# EX_POWER.net
KiCad netlist of a schematic drawn in Altium Designer
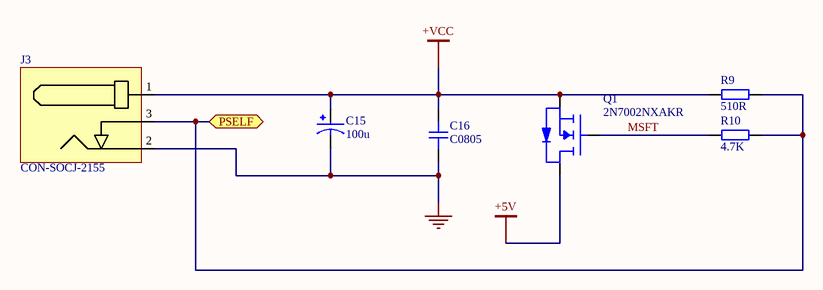
[diagram p0: EX_POWER.SchDoc]

(export (version "E")
  (design (tool "Eeschema 10.0.6"))
  (components
    (comp (ref "C15")
      (value "100u")
      (footprint "CAP_EEEHA0J101WR")
      (fields (field (name "MF") "Panasonic Electronic") (field (name "MP") "EEE-HA0J101WR"))
      (libsource (lib "Schematic-Lib-PhilsLab") (part "EEEHA0J101WR"))
    )
    (comp (ref "C16")
      (value "C0805")
      (footprint "CAP_0805")
      (description "Capacitor SMD 0805")
      (libsource (lib "Schematic-Lib-PhilsLab") (part "CAP_0805"))
    )
    (comp (ref "J3")
      (value "CON-SOCJ-2155")
      (footprint "CON-SOCJ-2155")
      (description "DC Barrell Jack 2.1mm 30V 2.5A THT")
      (fields (field (name "MANUFACTURER") "Gravitech"))
      (libsource (lib "Schematic-Lib-PhilsLab") (part "CON-SOCJ-2155"))
    )
    (comp (ref "Q1")
      (value "2N7002NXAKR")
      (footprint "SSM3J338R,LF-SOT23-F")
      (description "MOSFET N-Channel Vds=60V Id=300mA with ESD Protection")
      (fields (field (name "MANUFACTURER") "Nexperia"))
      (libsource (lib "Schematic-Lib-PhilsLab") (part "2N7002NXAKR"))
    )
    (comp (ref "R9")
      (value "510R")
      (footprint "RES_0603")
      (description "Resistor SMD 0603")
      (libsource (lib "Schematic-Lib-PhilsLab") (part "RES_0603"))
    )
    (comp (ref "R10")
      (value "4.7K")
      (footprint "RES_0603")
      (description "Resistor SMD 0603")
      (libsource (lib "Schematic-Lib-PhilsLab") (part "RES_0603"))
    )
  )
  (nets
    (net (code "1") (name "+5V") (class "Default")
      (node (ref "Q1") (pin "D") (pinfunction "D_D") (pintype "passive"))
    )
    (net (code "2") (name "+VCC") (class "Default")
      (node (ref "C15") (pin "1") (pinfunction "1_1") (pintype "passive"))
      (node (ref "C16") (pin "2") (pinfunction "2_2") (pintype "passive"))
      (node (ref "J3") (pin "1") (pinfunction "1_1") (pintype "passive"))
      (node (ref "Q1") (pin "S") (pinfunction "S_S") (pintype "passive"))
      (node (ref "R9") (pin "1") (pinfunction "1_1") (pintype "passive"))
    )
    (net (code "3") (name "/MSFT") (class "Default")
      (node (ref "Q1") (pin "G") (pinfunction "G_G") (pintype "passive"))
      (node (ref "R10") (pin "1") (pinfunction "1_1") (pintype "passive"))
    )
    (net (code "4") (name "/PSELF") (class "Default")
      (node (ref "J3") (pin "3") (pinfunction "3_3") (pintype "passive"))
      (node (ref "R10") (pin "2") (pinfunction "2_2") (pintype "passive"))
      (node (ref "R9") (pin "2") (pinfunction "2_2") (pintype "passive"))
    )
    (net (code "5") (name "GND") (class "Default")
      (node (ref "C15") (pin "2") (pinfunction "2_2") (pintype "passive"))
      (node (ref "C16") (pin "1") (pinfunction "1_1") (pintype "passive"))
      (node (ref "J3") (pin "2") (pinfunction "2_2") (pintype "passive"))
    )
  )
)
